# PCEMouse_rev_C.net
KiCad netlist of a schematic drawn in EAGLE
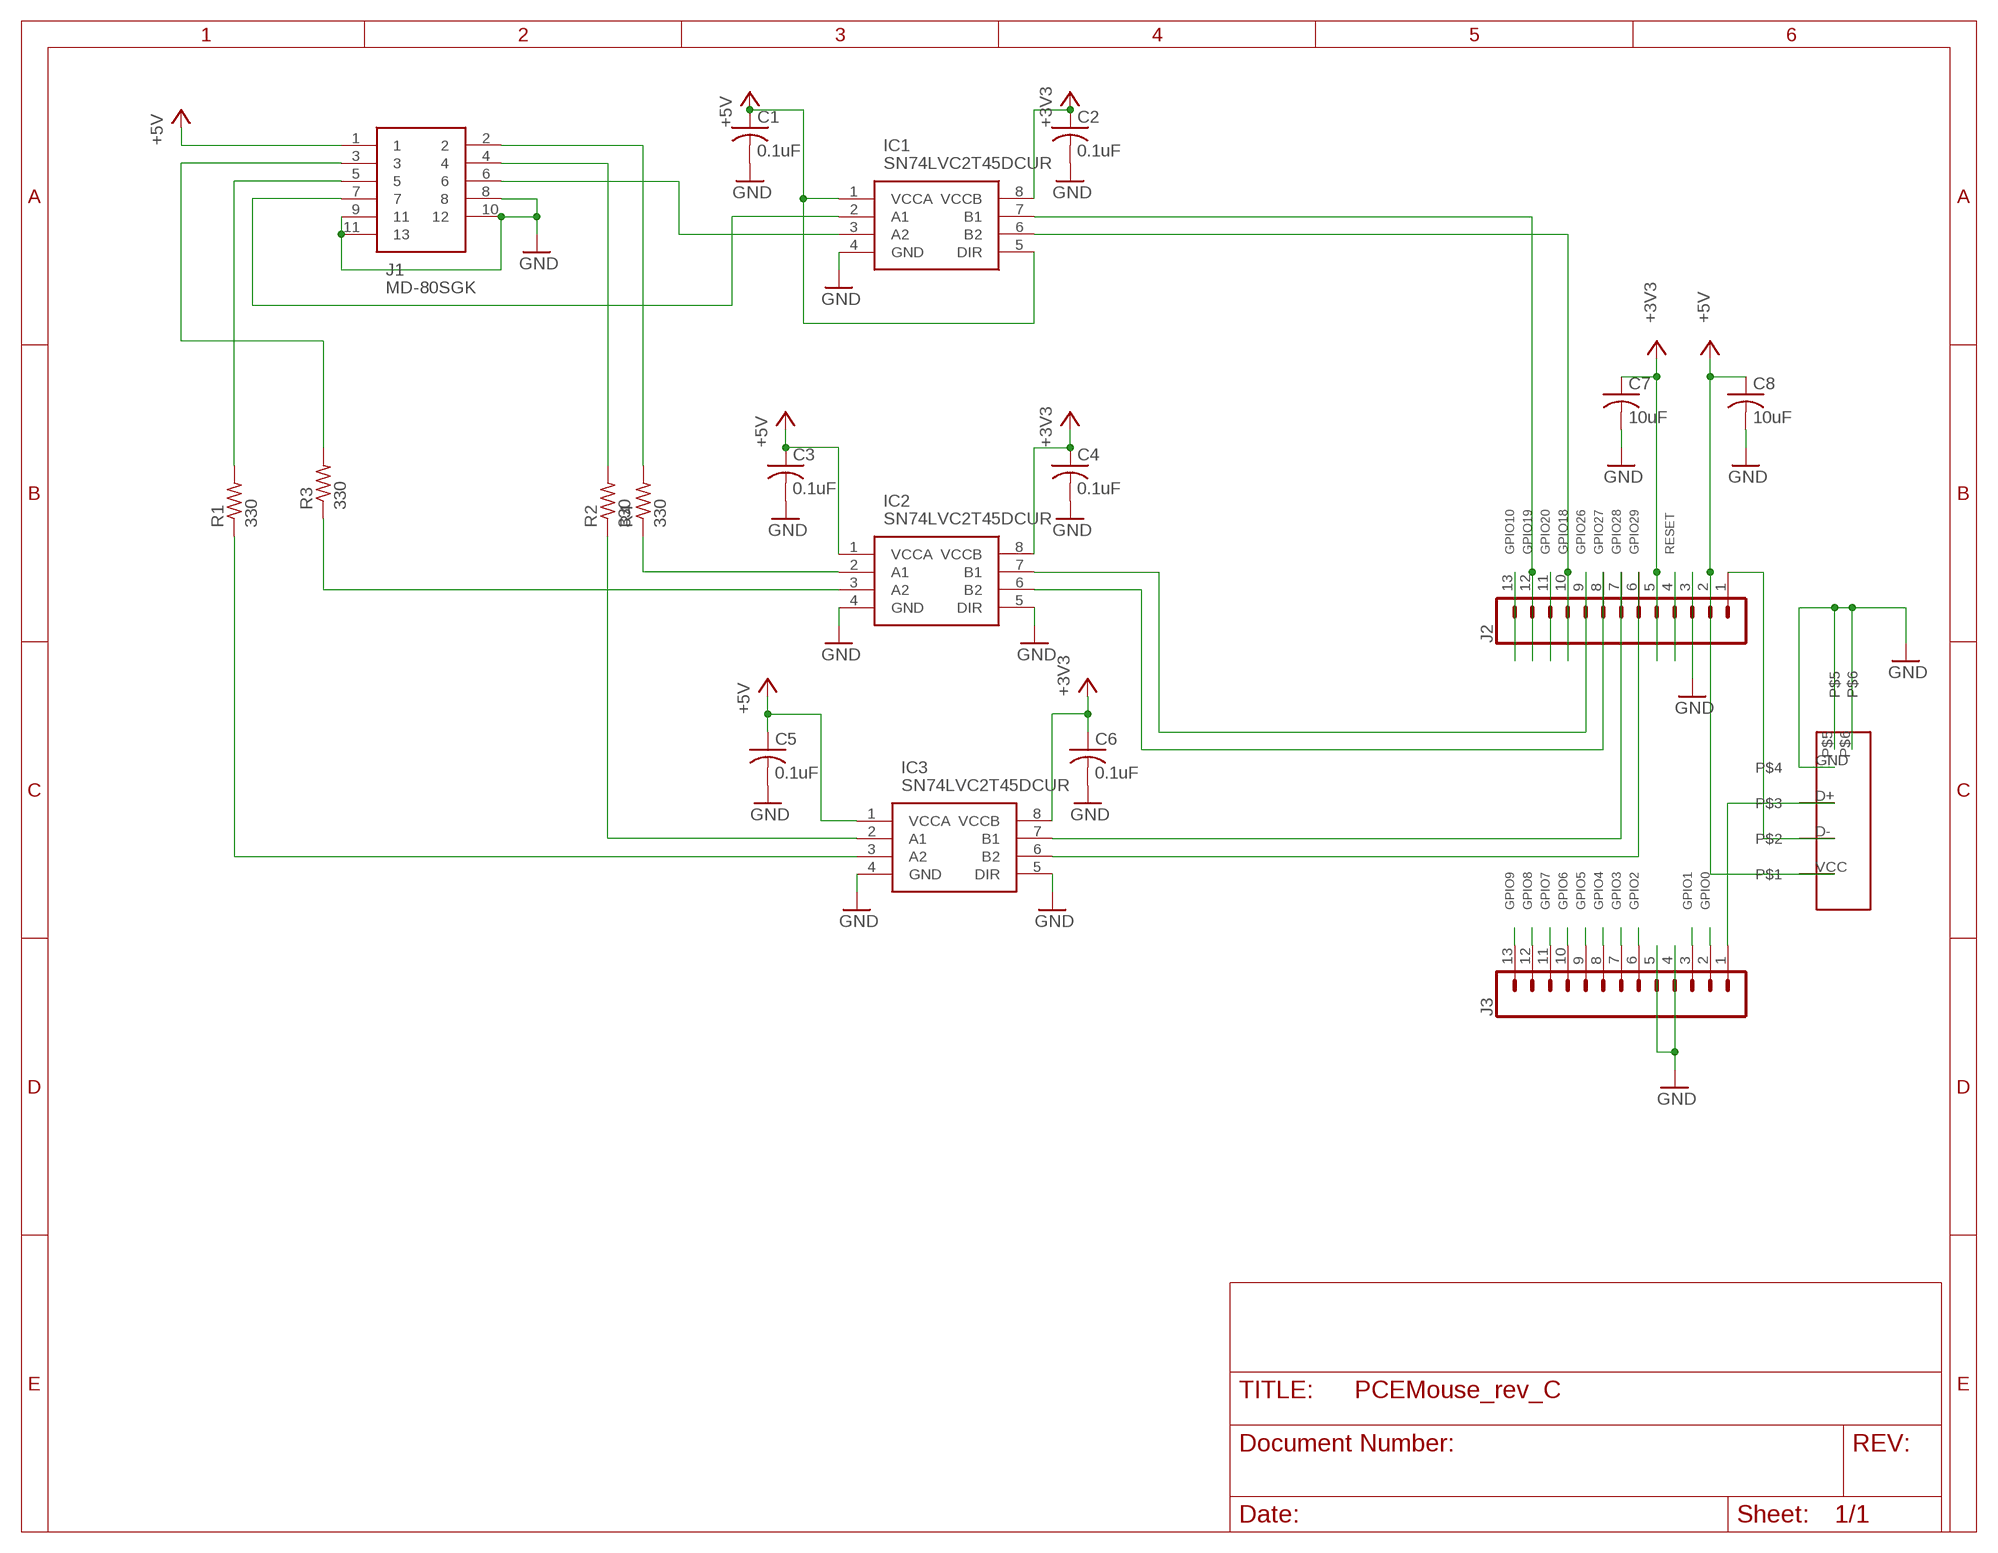
[diagram p0: schematic, sheet 1]

(export (version "E")
  (design (tool "Eeschema 10.0.6"))
  (components
    (comp (ref "C1")
      (value "0.1uF")
      (footprint "eagle-import:C0402")
      (libsource (lib "eagle-import") (part "C-USC0402"))
    )
    (comp (ref "C2")
      (value "0.1uF")
      (footprint "eagle-import:C0402")
      (libsource (lib "eagle-import") (part "C-USC0402"))
    )
    (comp (ref "C3")
      (value "0.1uF")
      (footprint "eagle-import:C0402")
      (libsource (lib "eagle-import") (part "C-USC0402"))
    )
    (comp (ref "C4")
      (value "0.1uF")
      (footprint "eagle-import:C0402")
      (libsource (lib "eagle-import") (part "C-USC0402"))
    )
    (comp (ref "C5")
      (value "0.1uF")
      (footprint "eagle-import:C0402")
      (libsource (lib "eagle-import") (part "C-USC0402"))
    )
    (comp (ref "C6")
      (value "0.1uF")
      (footprint "eagle-import:C0402")
      (libsource (lib "eagle-import") (part "C-USC0402"))
    )
    (comp (ref "C7")
      (value "10uF")
      (footprint "eagle-import:C0805")
      (libsource (lib "eagle-import") (part "resistor_348_C-USC0805"))
    )
    (comp (ref "C8")
      (value "10uF")
      (footprint "eagle-import:C0805")
      (libsource (lib "eagle-import") (part "resistor_348_C-USC0805"))
    )
    (comp (ref "IC1")
      (value "SN74LVC2T45DCUR")
      (footprint "eagle-import:SOP50P310X90-8N")
      (fields (field (name "MOUSER_PART_NUMBER") "595-SN74LVC2T45DCUR"))
      (libsource (lib "eagle-import") (part "SN74LVC2T45DCUR"))
    )
    (comp (ref "IC2")
      (value "SN74LVC2T45DCUR")
      (footprint "eagle-import:SOP50P310X90-8N")
      (fields (field (name "MOUSER_PART_NUMBER") "595-SN74LVC2T45DCUR"))
      (libsource (lib "eagle-import") (part "SN74LVC2T45DCUR"))
    )
    (comp (ref "IC3")
      (value "SN74LVC2T45DCUR")
      (footprint "eagle-import:SOP50P310X90-8N")
      (fields (field (name "MOUSER_PART_NUMBER") "595-SN74LVC2T45DCUR"))
      (libsource (lib "eagle-import") (part "SN74LVC2T45DCUR"))
    )
    (comp (ref "J1")
      (value "MD-80SGK")
      (footprint "eagle-import:MD80SGK")
      (fields (field (name "MOUSER_PART_NUMBER") "490-MD-80SGK"))
      (libsource (lib "eagle-import") (part "MD-80SGK"))
    )
    (comp (ref "J2")
      (value "CONN_13LONGPADS")
      (footprint "eagle-import:1X13-LONGPADS")
      (libsource (lib "eagle-import") (part "CONN_13LONGPADS"))
    )
    (comp (ref "J3")
      (value "CONN_13LONGPADS")
      (footprint "eagle-import:1X13-LONGPADS")
      (libsource (lib "eagle-import") (part "CONN_13LONGPADS"))
    )
    (comp (ref "R1")
      (value "330")
      (footprint "eagle-import:R0402")
      (libsource (lib "eagle-import") (part "R-US_R0402"))
    )
    (comp (ref "R2")
      (value "330")
      (footprint "eagle-import:R0402")
      (libsource (lib "eagle-import") (part "R-US_R0402"))
    )
    (comp (ref "R3")
      (value "330")
      (footprint "eagle-import:R0402")
      (libsource (lib "eagle-import") (part "R-US_R0402"))
    )
    (comp (ref "R4")
      (value "330")
      (footprint "eagle-import:R0402")
      (libsource (lib "eagle-import") (part "R-US_R0402"))
    )
    (comp (ref "U$1")
      (value "912-121A2026S10100")
      (footprint "eagle-import:912-121A2026S10100")
      (libsource (lib "eagle-import") (part "912-121A2026S10100"))
    )
  )
  (nets
    (net (code "1") (name "+3V3") (class "Default")
      (node (ref "C2") (pin "1") (pinfunction "1_1") (pintype "passive"))
      (node (ref "C4") (pin "1") (pinfunction "1_1") (pintype "passive"))
      (node (ref "C6") (pin "1") (pinfunction "1_1") (pintype "passive"))
      (node (ref "C7") (pin "1") (pinfunction "1_1") (pintype "passive"))
      (node (ref "IC1") (pin "8") (pinfunction "VCCB_8") (pintype "bidirectional"))
      (node (ref "IC2") (pin "8") (pinfunction "VCCB_8") (pintype "bidirectional"))
      (node (ref "IC3") (pin "8") (pinfunction "VCCB_8") (pintype "bidirectional"))
      (node (ref "J2") (pin "5") (pinfunction "5_5") (pintype "passive"))
    )
    (net (code "2") (name "+5V") (class "Default")
      (node (ref "C1") (pin "1") (pinfunction "1_1") (pintype "passive"))
      (node (ref "C3") (pin "1") (pinfunction "1_1") (pintype "passive"))
      (node (ref "C5") (pin "1") (pinfunction "1_1") (pintype "passive"))
      (node (ref "C8") (pin "1") (pinfunction "1_1") (pintype "passive"))
      (node (ref "IC1") (pin "1") (pinfunction "VCCA_1") (pintype "bidirectional"))
      (node (ref "IC1") (pin "5") (pinfunction "DIR_5") (pintype "bidirectional"))
      (node (ref "IC2") (pin "1") (pinfunction "VCCA_1") (pintype "bidirectional"))
      (node (ref "IC3") (pin "1") (pinfunction "VCCA_1") (pintype "bidirectional"))
      (node (ref "J1") (pin "1") (pinfunction "1_1") (pintype "bidirectional"))
      (node (ref "J2") (pin "2") (pinfunction "2_2") (pintype "passive"))
      (node (ref "U$1") (pin "VCC") (pinfunction "P$1_VCC") (pintype "bidirectional"))
    )
    (net (code "3") (name "/GPIO0") (class "Default")
      (node (ref "J3") (pin "2") (pinfunction "2_2") (pintype "passive"))
    )
    (net (code "4") (name "/GPIO1") (class "Default")
      (node (ref "J3") (pin "3") (pinfunction "3_3") (pintype "passive"))
    )
    (net (code "5") (name "/GPIO2") (class "Default")
      (node (ref "J3") (pin "6") (pinfunction "6_6") (pintype "passive"))
    )
    (net (code "6") (name "/GPIO3") (class "Default")
      (node (ref "J3") (pin "7") (pinfunction "7_7") (pintype "passive"))
    )
    (net (code "7") (name "/GPIO4") (class "Default")
      (node (ref "J3") (pin "8") (pinfunction "8_8") (pintype "passive"))
    )
    (net (code "8") (name "/GPIO5") (class "Default")
      (node (ref "J3") (pin "9") (pinfunction "9_9") (pintype "passive"))
    )
    (net (code "9") (name "/GPIO6") (class "Default")
      (node (ref "J3") (pin "10") (pinfunction "10_10") (pintype "passive"))
    )
    (net (code "10") (name "/GPIO7") (class "Default")
      (node (ref "J3") (pin "11") (pinfunction "11_11") (pintype "passive"))
    )
    (net (code "11") (name "/GPIO8") (class "Default")
      (node (ref "J3") (pin "12") (pinfunction "12_12") (pintype "passive"))
    )
    (net (code "12") (name "/GPIO9") (class "Default")
      (node (ref "J3") (pin "13") (pinfunction "13_13") (pintype "passive"))
    )
    (net (code "13") (name "/GPIO10") (class "Default")
      (node (ref "J2") (pin "13") (pinfunction "13_13") (pintype "passive"))
    )
    (net (code "14") (name "/GPIO18") (class "Default")
      (node (ref "IC1") (pin "6") (pinfunction "B2_6") (pintype "bidirectional"))
      (node (ref "J2") (pin "10") (pinfunction "10_10") (pintype "passive"))
    )
    (net (code "15") (name "/GPIO19") (class "Default")
      (node (ref "IC1") (pin "7") (pinfunction "B1_7") (pintype "bidirectional"))
      (node (ref "J2") (pin "12") (pinfunction "12_12") (pintype "passive"))
    )
    (net (code "16") (name "/GPIO20") (class "Default")
      (node (ref "J2") (pin "11") (pinfunction "11_11") (pintype "passive"))
    )
    (net (code "17") (name "/GPIO26") (class "Default")
      (node (ref "IC2") (pin "7") (pinfunction "B1_7") (pintype "bidirectional"))
      (node (ref "J2") (pin "9") (pinfunction "9_9") (pintype "passive"))
    )
    (net (code "18") (name "/GPIO27") (class "Default")
      (node (ref "IC2") (pin "6") (pinfunction "B2_6") (pintype "bidirectional"))
      (node (ref "J2") (pin "8") (pinfunction "8_8") (pintype "passive"))
    )
    (net (code "19") (name "/GPIO28") (class "Default")
      (node (ref "IC3") (pin "7") (pinfunction "B1_7") (pintype "bidirectional"))
      (node (ref "J2") (pin "7") (pinfunction "7_7") (pintype "passive"))
    )
    (net (code "20") (name "/GPIO29") (class "Default")
      (node (ref "IC3") (pin "6") (pinfunction "B2_6") (pintype "bidirectional"))
      (node (ref "J2") (pin "6") (pinfunction "6_6") (pintype "passive"))
    )
    (net (code "21") (name "/RESET") (class "Default")
      (node (ref "J2") (pin "4") (pinfunction "4_4") (pintype "passive"))
    )
    (net (code "22") (name "GND") (class "Default")
      (node (ref "C1") (pin "2") (pinfunction "2_2") (pintype "passive"))
      (node (ref "C2") (pin "2") (pinfunction "2_2") (pintype "passive"))
      (node (ref "C3") (pin "2") (pinfunction "2_2") (pintype "passive"))
      (node (ref "C4") (pin "2") (pinfunction "2_2") (pintype "passive"))
      (node (ref "C5") (pin "2") (pinfunction "2_2") (pintype "passive"))
      (node (ref "C6") (pin "2") (pinfunction "2_2") (pintype "passive"))
      (node (ref "C7") (pin "2") (pinfunction "2_2") (pintype "passive"))
      (node (ref "C8") (pin "2") (pinfunction "2_2") (pintype "passive"))
      (node (ref "IC1") (pin "4") (pinfunction "GND_4") (pintype "bidirectional"))
      (node (ref "IC2") (pin "4") (pinfunction "GND_4") (pintype "bidirectional"))
      (node (ref "IC2") (pin "5") (pinfunction "DIR_5") (pintype "bidirectional"))
      (node (ref "IC3") (pin "4") (pinfunction "GND_4") (pintype "bidirectional"))
      (node (ref "IC3") (pin "5") (pinfunction "DIR_5") (pintype "bidirectional"))
      (node (ref "J1") (pin "10") (pinfunction "12_10") (pintype "bidirectional"))
      (node (ref "J1") (pin "11") (pinfunction "13_11") (pintype "bidirectional"))
      (node (ref "J1") (pin "8") (pinfunction "8_8") (pintype "bidirectional"))
      (node (ref "J1") (pin "9") (pinfunction "11_9") (pintype "bidirectional"))
      (node (ref "J2") (pin "3") (pinfunction "3_3") (pintype "passive"))
      (node (ref "J3") (pin "4") (pinfunction "4_4") (pintype "passive"))
      (node (ref "J3") (pin "5") (pinfunction "5_5") (pintype "passive"))
      (node (ref "U$1") (pin "GND") (pinfunction "P$4_GND") (pintype "bidirectional"))
      (node (ref "U$1") (pin "P$5") (pinfunction "P$5_P$5") (pintype "bidirectional"))
      (node (ref "U$1") (pin "P$6") (pinfunction "P$6_P$6") (pintype "bidirectional"))
    )
    (net (code "23") (name "Net-(IC1-A1)") (class "Default")
      (node (ref "IC1") (pin "2") (pinfunction "A1_2") (pintype "bidirectional"))
      (node (ref "J1") (pin "7") (pinfunction "7_7") (pintype "bidirectional"))
    )
    (net (code "24") (name "Net-(IC1-A2)") (class "Default")
      (node (ref "IC1") (pin "3") (pinfunction "A2_3") (pintype "bidirectional"))
      (node (ref "J1") (pin "6") (pinfunction "6_6") (pintype "bidirectional"))
    )
    (net (code "25") (name "Net-(IC2-A1)") (class "Default")
      (node (ref "IC2") (pin "2") (pinfunction "A1_2") (pintype "bidirectional"))
      (node (ref "R4") (pin "1") (pinfunction "1_1") (pintype "passive"))
    )
    (net (code "26") (name "Net-(IC2-A2)") (class "Default")
      (node (ref "IC2") (pin "3") (pinfunction "A2_3") (pintype "bidirectional"))
      (node (ref "R3") (pin "1") (pinfunction "1_1") (pintype "passive"))
    )
    (net (code "27") (name "Net-(IC3-A1)") (class "Default")
      (node (ref "IC3") (pin "2") (pinfunction "A1_2") (pintype "bidirectional"))
      (node (ref "R2") (pin "1") (pinfunction "1_1") (pintype "passive"))
    )
    (net (code "28") (name "Net-(IC3-A2)") (class "Default")
      (node (ref "IC3") (pin "3") (pinfunction "A2_3") (pintype "bidirectional"))
      (node (ref "R1") (pin "1") (pinfunction "1_1") (pintype "passive"))
    )
    (net (code "29") (name "Net-(J1-Pad2)") (class "Default")
      (node (ref "J1") (pin "2") (pinfunction "2_2") (pintype "bidirectional"))
      (node (ref "R4") (pin "2") (pinfunction "2_2") (pintype "passive"))
    )
    (net (code "30") (name "Net-(J1-Pad3)") (class "Default")
      (node (ref "J1") (pin "3") (pinfunction "3_3") (pintype "bidirectional"))
      (node (ref "R3") (pin "2") (pinfunction "2_2") (pintype "passive"))
    )
    (net (code "31") (name "Net-(J1-Pad4)") (class "Default")
      (node (ref "J1") (pin "4") (pinfunction "4_4") (pintype "bidirectional"))
      (node (ref "R2") (pin "2") (pinfunction "2_2") (pintype "passive"))
    )
    (net (code "32") (name "Net-(J1-Pad5)") (class "Default")
      (node (ref "J1") (pin "5") (pinfunction "5_5") (pintype "bidirectional"))
      (node (ref "R1") (pin "2") (pinfunction "2_2") (pintype "passive"))
    )
    (net (code "33") (name "Net-(U$1-P$2)") (class "Default")
      (node (ref "J2") (pin "1") (pinfunction "1_1") (pintype "passive"))
      (node (ref "U$1") (pin "D-") (pinfunction "P$2_D-") (pintype "bidirectional"))
    )
    (net (code "34") (name "Net-(U$1-P$3)") (class "Default")
      (node (ref "J3") (pin "1") (pinfunction "1_1") (pintype "passive"))
      (node (ref "U$1") (pin "D+") (pinfunction "P$3_D+") (pintype "bidirectional"))
    )
  )
)
